# sound_modem_sch.net
KiCad netlist of a schematic drawn in EAGLE
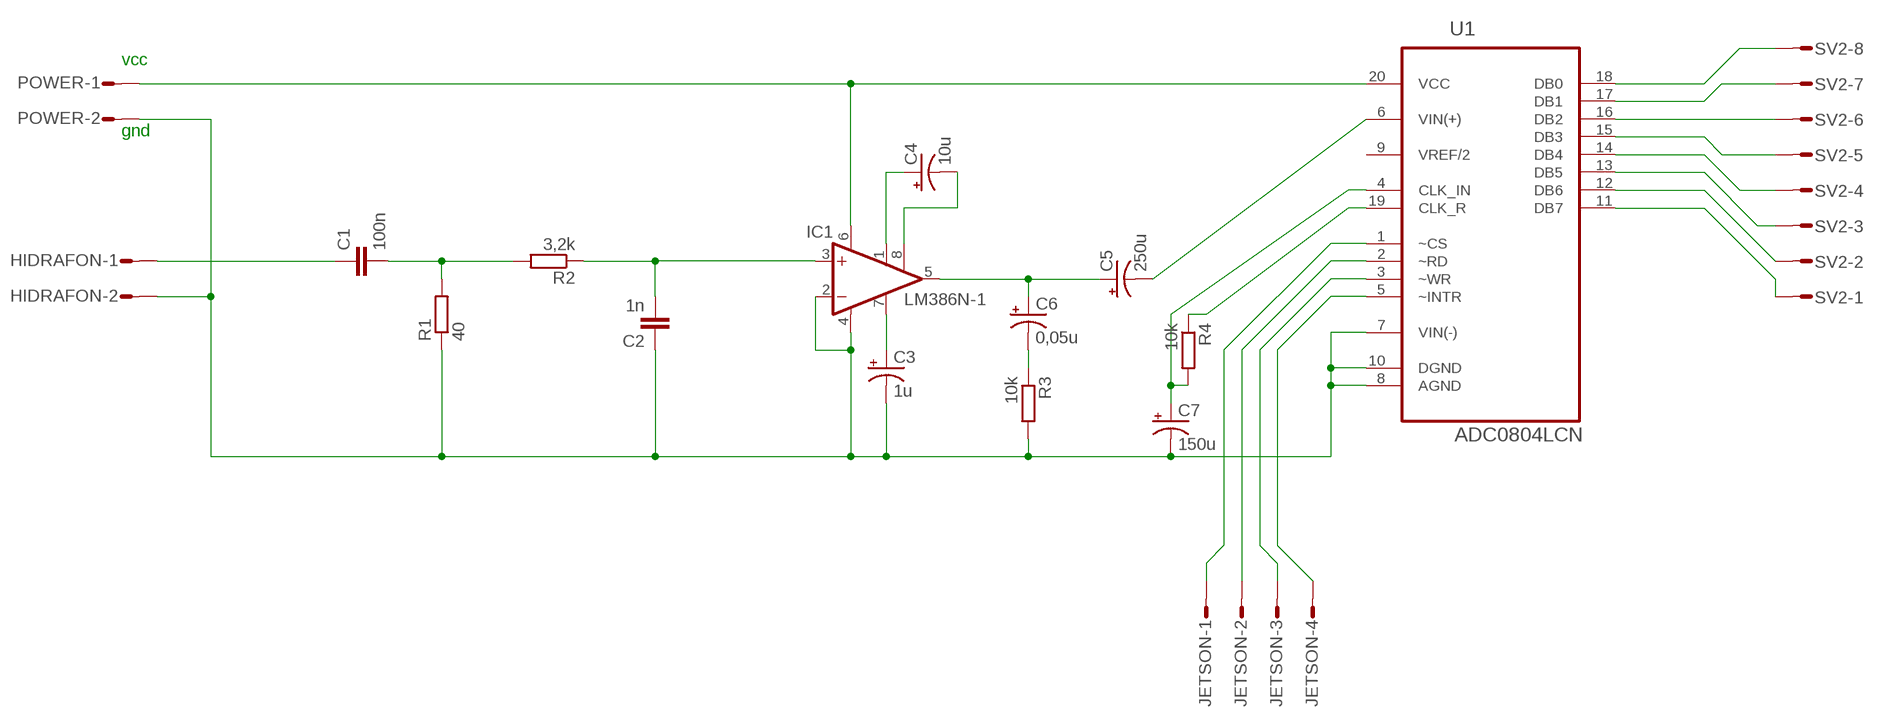
[diagram p0: schematic, sheet 1]

(export (version "E")
  (design (tool "Eeschema 10.0.6"))
  (components
    (comp (ref "C1")
      (value "100n")
      (footprint "eagle-import:C025-025X050")
      (libsource (lib "eagle-import") (part "C-EU025-025X050"))
    )
    (comp (ref "C2")
      (value "1n")
      (footprint "eagle-import:C025-025X050")
      (libsource (lib "eagle-import") (part "C-EU025-025X050"))
    )
    (comp (ref "C3")
      (value "1u")
      (footprint "eagle-import:E2-5")
      (libsource (lib "eagle-import") (part "CPOL-USE2-5"))
    )
    (comp (ref "C4")
      (value "10u")
      (footprint "eagle-import:E2-5")
      (libsource (lib "eagle-import") (part "CPOL-USE2-5"))
    )
    (comp (ref "C5")
      (value "250u")
      (footprint "eagle-import:E5-10,5")
      (libsource (lib "eagle-import") (part "CPOL-USE5-10.5"))
    )
    (comp (ref "C6")
      (value "0,05u")
      (footprint "eagle-import:E2-5")
      (libsource (lib "eagle-import") (part "CPOL-USE2-5"))
    )
    (comp (ref "C7")
      (value "150u")
      (footprint "eagle-import:E5-10,5")
      (libsource (lib "eagle-import") (part "CPOL-USE5-10.5"))
    )
    (comp (ref "HIDRAFON")
      (value "L02P")
      (footprint "eagle-import:L02P")
      (libsource (lib "eagle-import") (part "L02P"))
    )
    (comp (ref "IC1")
      (value "LM386N-1")
      (footprint "eagle-import:DIL08")
      (libsource (lib "eagle-import") (part "LM386?-N1"))
    )
    (comp (ref "JETSON")
      (value "L04P")
      (footprint "eagle-import:L04P")
      (libsource (lib "eagle-import") (part "L04P"))
    )
    (comp (ref "POWER")
      (value "L02P")
      (footprint "eagle-import:L02P")
      (libsource (lib "eagle-import") (part "L02P"))
    )
    (comp (ref "R1")
      (value "40")
      (footprint "eagle-import:0204_7")
      (libsource (lib "eagle-import") (part "R-EU_0204/7"))
    )
    (comp (ref "R2")
      (value "3,2k")
      (footprint "eagle-import:0204_7")
      (libsource (lib "eagle-import") (part "R-EU_0204/7"))
    )
    (comp (ref "R3")
      (value "10k")
      (footprint "eagle-import:0204_7")
      (libsource (lib "eagle-import") (part "R-EU_0204/7"))
    )
    (comp (ref "R4")
      (value "10k")
      (footprint "eagle-import:0204_7")
      (libsource (lib "eagle-import") (part "R-EU_0204/7"))
    )
    (comp (ref "SV2")
      (value "L08P")
      (footprint "eagle-import:L08P")
      (libsource (lib "eagle-import") (part "L08P"))
    )
    (comp (ref "U1")
      (value "ADC0804LCN")
      (footprint "eagle-import:DIP254P762X508-20")
      (fields (field (name "MF") "Texas Instruments"))
      (libsource (lib "eagle-import") (part "ADC0804LCN"))
    )
  )
  (nets
    (net (code "1") (name "Net-(C1-Pad2)") (class "Default")
      (node (ref "C1") (pin "2") (pinfunction "2_2") (pintype "passive"))
      (node (ref "R1") (pin "2") (pinfunction "2_2") (pintype "passive"))
      (node (ref "R2") (pin "2") (pinfunction "2_2") (pintype "passive"))
    )
    (net (code "2") (name "Net-(C4-Pad+)") (class "Default")
      (node (ref "C4") (pin "+") (pinfunction "+_+") (pintype "passive"))
      (node (ref "IC1") (pin "1") (pinfunction "GAIN_1") (pintype "passive"))
    )
    (net (code "3") (name "Net-(C4-Pad-)") (class "Default")
      (node (ref "C4") (pin "-") (pinfunction "-_-") (pintype "passive"))
      (node (ref "IC1") (pin "8") (pinfunction "GAIN_8") (pintype "passive"))
    )
    (net (code "4") (name "Net-(C6-Pad-)") (class "Default")
      (node (ref "C6") (pin "-") (pinfunction "-_-") (pintype "passive"))
      (node (ref "R3") (pin "1") (pinfunction "1_1") (pintype "passive"))
    )
    (net (code "5") (name "Net-(HIDRAFONA-S)") (class "Default")
      (node (ref "C1") (pin "1") (pinfunction "1_1") (pintype "passive"))
      (node (ref "HIDRAFON") (pin "1") (pinfunction "S_1") (pintype "passive"))
    )
    (net (code "6") (name "Net-(HIDRAFONB-S)") (class "Default")
      (node (ref "C2") (pin "1") (pinfunction "1_1") (pintype "passive"))
      (node (ref "C3") (pin "-") (pinfunction "-_-") (pintype "passive"))
      (node (ref "C7") (pin "-") (pinfunction "-_-") (pintype "passive"))
      (node (ref "HIDRAFON") (pin "2") (pinfunction "S_2") (pintype "passive"))
      (node (ref "IC1") (pin "2") (pinfunction "-IN_2") (pintype "input"))
      (node (ref "IC1") (pin "4") (pinfunction "GND_4") (pintype "power_in"))
      (node (ref "POWER") (pin "2") (pinfunction "S_2") (pintype "passive"))
      (node (ref "R1") (pin "1") (pinfunction "1_1") (pintype "passive"))
      (node (ref "R3") (pin "2") (pinfunction "2_2") (pintype "passive"))
      (node (ref "U1") (pin "10") (pinfunction "DGND_10") (pintype "passive"))
      (node (ref "U1") (pin "7") (pinfunction "VIN(-)_7") (pintype "power_in"))
      (node (ref "U1") (pin "8") (pinfunction "AGND_8") (pintype "passive"))
    )
    (net (code "7") (name "Net-(IC1-+IN)") (class "Default")
      (node (ref "C2") (pin "2") (pinfunction "2_2") (pintype "passive"))
      (node (ref "IC1") (pin "3") (pinfunction "+IN_3") (pintype "input"))
      (node (ref "R2") (pin "1") (pinfunction "1_1") (pintype "passive"))
    )
    (net (code "8") (name "Net-(IC1-BYPASS)") (class "Default")
      (node (ref "C3") (pin "+") (pinfunction "+_+") (pintype "passive"))
      (node (ref "IC1") (pin "7") (pinfunction "BYPASS_7") (pintype "passive"))
    )
    (net (code "9") (name "Net-(IC1-OUT)") (class "Default")
      (node (ref "C5") (pin "+") (pinfunction "+_+") (pintype "passive"))
      (node (ref "C6") (pin "+") (pinfunction "+_+") (pintype "passive"))
      (node (ref "IC1") (pin "5") (pinfunction "OUT_5") (pintype "output"))
    )
    (net (code "10") (name "Net-(IC1-VS)") (class "Default")
      (node (ref "IC1") (pin "6") (pinfunction "VS_6") (pintype "power_in"))
      (node (ref "POWER") (pin "1") (pinfunction "S_1") (pintype "passive"))
      (node (ref "U1") (pin "20") (pinfunction "VCC_20") (pintype "power_in"))
    )
    (net (code "11") (name "Net-(JETSONA-S)") (class "Default")
      (node (ref "JETSON") (pin "1") (pinfunction "S_1") (pintype "passive"))
      (node (ref "U1") (pin "1") (pinfunction "~{CS}_1") (pintype "input"))
    )
    (net (code "12") (name "Net-(JETSONB-S)") (class "Default")
      (node (ref "JETSON") (pin "2") (pinfunction "S_2") (pintype "passive"))
      (node (ref "U1") (pin "2") (pinfunction "~{RD}_2") (pintype "input"))
    )
    (net (code "13") (name "Net-(JETSONC-S)") (class "Default")
      (node (ref "JETSON") (pin "3") (pinfunction "S_3") (pintype "passive"))
      (node (ref "U1") (pin "3") (pinfunction "~{WR}_3") (pintype "input"))
    )
    (net (code "14") (name "Net-(JETSOND-S)") (class "Default")
      (node (ref "JETSON") (pin "4") (pinfunction "S_4") (pintype "passive"))
      (node (ref "U1") (pin "5") (pinfunction "~{INTR}_5") (pintype "input"))
    )
    (net (code "15") (name "Net-(SV2A-S)") (class "Default")
      (node (ref "SV2") (pin "1") (pinfunction "S_1") (pintype "passive"))
      (node (ref "U1") (pin "11") (pinfunction "DB7_11") (pintype "passive"))
    )
    (net (code "16") (name "Net-(SV2B-S)") (class "Default")
      (node (ref "SV2") (pin "2") (pinfunction "S_2") (pintype "passive"))
      (node (ref "U1") (pin "12") (pinfunction "DB6_12") (pintype "passive"))
    )
    (net (code "17") (name "Net-(SV2C-S)") (class "Default")
      (node (ref "SV2") (pin "3") (pinfunction "S_3") (pintype "passive"))
      (node (ref "U1") (pin "13") (pinfunction "DB5_13") (pintype "passive"))
    )
    (net (code "18") (name "Net-(SV2D-S)") (class "Default")
      (node (ref "SV2") (pin "4") (pinfunction "S_4") (pintype "passive"))
      (node (ref "U1") (pin "14") (pinfunction "DB4_14") (pintype "passive"))
    )
    (net (code "19") (name "Net-(SV2E-S)") (class "Default")
      (node (ref "SV2") (pin "5") (pinfunction "S_5") (pintype "passive"))
      (node (ref "U1") (pin "15") (pinfunction "DB3_15") (pintype "passive"))
    )
    (net (code "20") (name "Net-(SV2F-S)") (class "Default")
      (node (ref "SV2") (pin "6") (pinfunction "S_6") (pintype "passive"))
      (node (ref "U1") (pin "16") (pinfunction "DB2_16") (pintype "passive"))
    )
    (net (code "21") (name "Net-(SV2G-S)") (class "Default")
      (node (ref "SV2") (pin "7") (pinfunction "S_7") (pintype "passive"))
      (node (ref "U1") (pin "17") (pinfunction "DB1_17") (pintype "passive"))
    )
    (net (code "22") (name "Net-(SV2H-S)") (class "Default")
      (node (ref "SV2") (pin "8") (pinfunction "S_8") (pintype "passive"))
      (node (ref "U1") (pin "18") (pinfunction "DB0_18") (pintype "passive"))
    )
    (net (code "23") (name "Net-(U1-CLK_IN)") (class "Default")
      (node (ref "C7") (pin "+") (pinfunction "+_+") (pintype "passive"))
      (node (ref "R4") (pin "2") (pinfunction "2_2") (pintype "passive"))
      (node (ref "U1") (pin "4") (pinfunction "CLK_IN_4") (pintype "input"))
    )
    (net (code "24") (name "Net-(U1-CLK_R)") (class "Default")
      (node (ref "R4") (pin "1") (pinfunction "1_1") (pintype "passive"))
      (node (ref "U1") (pin "19") (pinfunction "CLK_R_19") (pintype "input"))
    )
    (net (code "25") (name "Net-(U1-VIN(+))") (class "Default")
      (node (ref "C5") (pin "-") (pinfunction "-_-") (pintype "passive"))
      (node (ref "U1") (pin "6") (pinfunction "VIN(+)_6") (pintype "power_in"))
    )
    (net (code "26") (name "unconnected-(U1-VREF{slash}2-Pad9)") (class "Default")
      (node (ref "U1") (pin "9") (pinfunction "VREF/2_9") (pintype "input"))
    )
  )
)
